# Gas.net
KiCad netlist of a schematic drawn in EAGLE
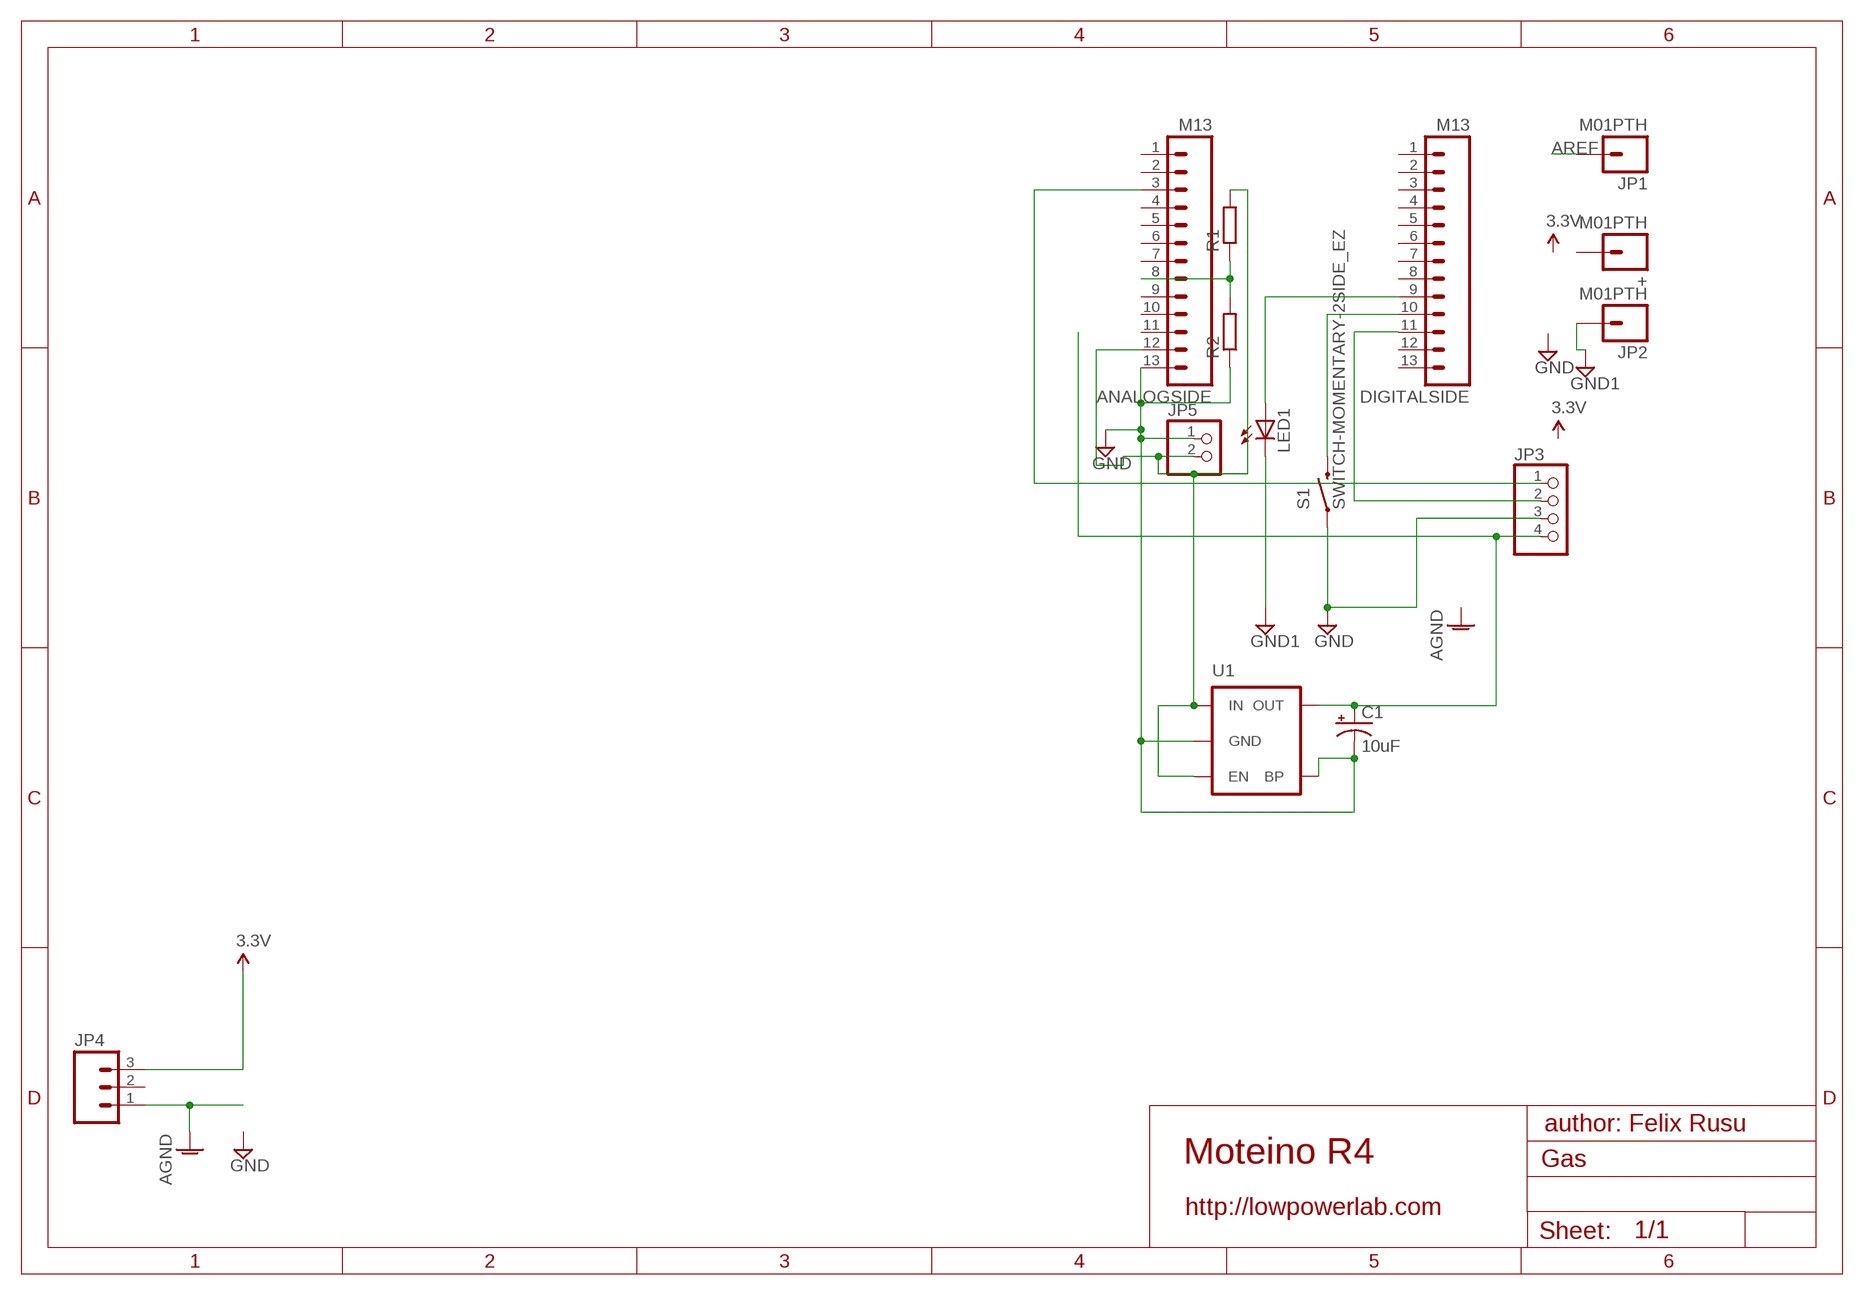
[diagram p0: schematic, sheet 1]

(export (version "E")
  (design (tool "Eeschema 10.0.6"))
  (components
    (comp (ref "+")
      (value "M01PTH")
      (footprint "eagle-import:1X01")
      (libsource (lib "eagle-import") (part "M01PTH"))
    )
    (comp (ref "ANALOGSIDE")
      (value "M13")
      (footprint "eagle-import:1X13")
      (libsource (lib "eagle-import") (part "M13"))
    )
    (comp (ref "C1")
      (value "10uF")
      (footprint "eagle-import:EIA3216")
      (libsource (lib "eagle-import") (part "10UF-16V-10%(TANT)"))
    )
    (comp (ref "DIGITALSIDE")
      (value "M13")
      (footprint "eagle-import:1X13")
      (libsource (lib "eagle-import") (part "M13"))
    )
    (comp (ref "JP1")
      (value "M01PTH")
      (footprint "eagle-import:1X01")
      (libsource (lib "eagle-import") (part "M01PTH"))
    )
    (comp (ref "JP2")
      (value "M01PTH")
      (footprint "eagle-import:1X01")
      (libsource (lib "eagle-import") (part "M01PTH"))
    )
    (comp (ref "JP3")
      (value "PINHD-1X4")
      (footprint "eagle-import:1X04")
      (libsource (lib "eagle-import") (part "PINHD-1X4"))
    )
    (comp (ref "JP4")
      (value "M03PTH")
      (footprint "eagle-import:1X03")
      (libsource (lib "eagle-import") (part "M03PTH"))
    )
    (comp (ref "JP5")
      (value "PINHD-1X2")
      (footprint "eagle-import:1X02")
      (libsource (lib "eagle-import") (part "PINHD-1X2"))
    )
    (comp (ref "LED1")
      (value "LED3MM")
      (footprint "eagle-import:LED3MM")
      (libsource (lib "eagle-import") (part "LED3MM"))
    )
    (comp (ref "R1")
      (value "R-EU_0204/7")
      (footprint "eagle-import:0204_7")
      (libsource (lib "eagle-import") (part "R-EU_0204/7"))
    )
    (comp (ref "R2")
      (value "R-EU_0204/7")
      (footprint "eagle-import:0204_7")
      (libsource (lib "eagle-import") (part "R-EU_0204/7"))
    )
    (comp (ref "S1")
      (value "SWITCH-MOMENTARY-2SIDE_EZ")
      (footprint "eagle-import:TACTILE-PTH-SIDEEZ")
      (libsource (lib "eagle-import") (part "SWITCH-MOMENTARY-2SIDE_EZ"))
    )
    (comp (ref "U1")
      (value "MIC52055V")
      (footprint "eagle-import:SOT23-5")
      (libsource (lib "eagle-import") (part "MIC52055V"))
    )
  )
  (nets
    (net (code "1") (name "/AREF") (class "Default")
      (node (ref "JP1") (pin "1") (pinfunction "1_1") (pintype "passive"))
    )
    (net (code "2") (name "3.3V") (class "Default")
      (node (ref "JP4") (pin "3") (pinfunction "3_3") (pintype "passive"))
    )
    (net (code "3") (name "AGND") (class "Default")
      (node (ref "JP4") (pin "1") (pinfunction "1_1") (pintype "passive"))
    )
    (net (code "4") (name "GND") (class "Default")
      (node (ref "ANALOGSIDE") (pin "13") (pinfunction "13_13") (pintype "passive"))
      (node (ref "C1") (pin "C") (pinfunction "-_C") (pintype "passive"))
      (node (ref "JP3") (pin "3") (pinfunction "3_3") (pintype "passive"))
      (node (ref "JP5") (pin "1") (pinfunction "1_1") (pintype "passive"))
      (node (ref "R2") (pin "1") (pinfunction "1_1") (pintype "passive"))
      (node (ref "S1") (pin "1") (pinfunction "1_1") (pintype "passive"))
      (node (ref "U1") (pin "2") (pinfunction "GND_2") (pintype "input"))
      (node (ref "U1") (pin "4") (pinfunction "BP_4") (pintype "input"))
    )
    (net (code "5") (name "GND1") (class "Default")
      (node (ref "JP2") (pin "1") (pinfunction "1_1") (pintype "passive"))
      (node (ref "LED1") (pin "K") (pinfunction "C_K") (pintype "passive"))
    )
    (net (code "6") (name "Net-(ANALOGSIDE-Pad3)") (class "Default")
      (node (ref "ANALOGSIDE") (pin "3") (pinfunction "3_3") (pintype "passive"))
      (node (ref "JP3") (pin "1") (pinfunction "1_1") (pintype "passive"))
    )
    (net (code "7") (name "Net-(ANALOGSIDE-Pad8)") (class "Default")
      (node (ref "ANALOGSIDE") (pin "8") (pinfunction "8_8") (pintype "passive"))
      (node (ref "R1") (pin "1") (pinfunction "1_1") (pintype "passive"))
      (node (ref "R2") (pin "2") (pinfunction "2_2") (pintype "passive"))
    )
    (net (code "8") (name "Net-(C1-+)") (class "Default")
      (node (ref "C1") (pin "A") (pinfunction "+_A") (pintype "passive"))
      (node (ref "JP3") (pin "4") (pinfunction "4_4") (pintype "passive"))
      (node (ref "U1") (pin "5") (pinfunction "OUT_5") (pintype "passive"))
    )
    (net (code "9") (name "Net-(DIGITALSIDE-Pad9)") (class "Default")
      (node (ref "DIGITALSIDE") (pin "9") (pinfunction "9_9") (pintype "passive"))
      (node (ref "LED1") (pin "A") (pinfunction "A_A") (pintype "passive"))
    )
    (net (code "10") (name "Net-(DIGITALSIDE-Pad10)") (class "Default")
      (node (ref "DIGITALSIDE") (pin "10") (pinfunction "10_10") (pintype "passive"))
      (node (ref "S1") (pin "2") (pinfunction "2_2") (pintype "passive"))
    )
    (net (code "11") (name "Net-(DIGITALSIDE-Pad11)") (class "Default")
      (node (ref "DIGITALSIDE") (pin "11") (pinfunction "11_11") (pintype "passive"))
      (node (ref "JP3") (pin "2") (pinfunction "2_2") (pintype "passive"))
    )
    (net (code "12") (name "Net-(U1-EN)") (class "Default")
      (node (ref "ANALOGSIDE") (pin "12") (pinfunction "12_12") (pintype "passive"))
      (node (ref "JP5") (pin "2") (pinfunction "2_2") (pintype "passive"))
      (node (ref "R1") (pin "2") (pinfunction "2_2") (pintype "passive"))
      (node (ref "U1") (pin "1") (pinfunction "IN_1") (pintype "input"))
      (node (ref "U1") (pin "3") (pinfunction "EN_3") (pintype "input"))
    )
    (net (code "13") (name "unconnected-(+-Pad1)") (class "Default")
      (node (ref "+") (pin "1") (pinfunction "1_1") (pintype "passive"))
    )
    (net (code "14") (name "unconnected-(ANALOGSIDE-Pad1)") (class "Default")
      (node (ref "ANALOGSIDE") (pin "1") (pinfunction "1_1") (pintype "passive"))
    )
    (net (code "15") (name "unconnected-(ANALOGSIDE-Pad2)") (class "Default")
      (node (ref "ANALOGSIDE") (pin "2") (pinfunction "2_2") (pintype "passive"))
    )
    (net (code "16") (name "unconnected-(ANALOGSIDE-Pad4)") (class "Default")
      (node (ref "ANALOGSIDE") (pin "4") (pinfunction "4_4") (pintype "passive"))
    )
    (net (code "17") (name "unconnected-(ANALOGSIDE-Pad5)") (class "Default")
      (node (ref "ANALOGSIDE") (pin "5") (pinfunction "5_5") (pintype "passive"))
    )
    (net (code "18") (name "unconnected-(ANALOGSIDE-Pad6)") (class "Default")
      (node (ref "ANALOGSIDE") (pin "6") (pinfunction "6_6") (pintype "passive"))
    )
    (net (code "19") (name "unconnected-(ANALOGSIDE-Pad7)") (class "Default")
      (node (ref "ANALOGSIDE") (pin "7") (pinfunction "7_7") (pintype "passive"))
    )
    (net (code "20") (name "unconnected-(ANALOGSIDE-Pad9)") (class "Default")
      (node (ref "ANALOGSIDE") (pin "9") (pinfunction "9_9") (pintype "passive"))
    )
    (net (code "21") (name "unconnected-(ANALOGSIDE-Pad10)") (class "Default")
      (node (ref "ANALOGSIDE") (pin "10") (pinfunction "10_10") (pintype "passive"))
    )
    (net (code "22") (name "unconnected-(ANALOGSIDE-Pad11)") (class "Default")
      (node (ref "ANALOGSIDE") (pin "11") (pinfunction "11_11") (pintype "passive"))
    )
    (net (code "23") (name "unconnected-(DIGITALSIDE-Pad1)") (class "Default")
      (node (ref "DIGITALSIDE") (pin "1") (pinfunction "1_1") (pintype "passive"))
    )
    (net (code "24") (name "unconnected-(DIGITALSIDE-Pad2)") (class "Default")
      (node (ref "DIGITALSIDE") (pin "2") (pinfunction "2_2") (pintype "passive"))
    )
    (net (code "25") (name "unconnected-(DIGITALSIDE-Pad3)") (class "Default")
      (node (ref "DIGITALSIDE") (pin "3") (pinfunction "3_3") (pintype "passive"))
    )
    (net (code "26") (name "unconnected-(DIGITALSIDE-Pad4)") (class "Default")
      (node (ref "DIGITALSIDE") (pin "4") (pinfunction "4_4") (pintype "passive"))
    )
    (net (code "27") (name "unconnected-(DIGITALSIDE-Pad5)") (class "Default")
      (node (ref "DIGITALSIDE") (pin "5") (pinfunction "5_5") (pintype "passive"))
    )
    (net (code "28") (name "unconnected-(DIGITALSIDE-Pad6)") (class "Default")
      (node (ref "DIGITALSIDE") (pin "6") (pinfunction "6_6") (pintype "passive"))
    )
    (net (code "29") (name "unconnected-(DIGITALSIDE-Pad7)") (class "Default")
      (node (ref "DIGITALSIDE") (pin "7") (pinfunction "7_7") (pintype "passive"))
    )
    (net (code "30") (name "unconnected-(DIGITALSIDE-Pad8)") (class "Default")
      (node (ref "DIGITALSIDE") (pin "8") (pinfunction "8_8") (pintype "passive"))
    )
    (net (code "31") (name "unconnected-(DIGITALSIDE-Pad12)") (class "Default")
      (node (ref "DIGITALSIDE") (pin "12") (pinfunction "12_12") (pintype "passive"))
    )
    (net (code "32") (name "unconnected-(DIGITALSIDE-Pad13)") (class "Default")
      (node (ref "DIGITALSIDE") (pin "13") (pinfunction "13_13") (pintype "passive"))
    )
    (net (code "33") (name "unconnected-(JP4-Pad2)") (class "Default")
      (node (ref "JP4") (pin "2") (pinfunction "2_2") (pintype "passive"))
    )
  )
)
